# Regulator_3_3V.net
KiCad netlist of a schematic drawn in Altium Designer
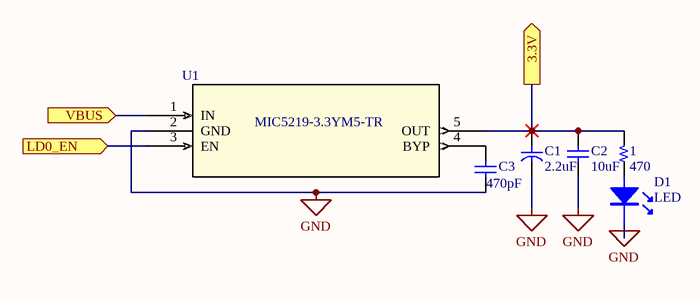
[diagram p0: Regulator 3.3V.SchDoc]

(export (version "E")
  (design (tool "Eeschema 10.0.6"))
  (components
    (comp (ref "1")
      (value "470")
      (footprint "R 0805")
      (description "Resistor")
      (libsource (lib "chipfc_libs") (part "Resistor"))
    )
    (comp (ref "C1")
      (value "2.2uF")
      (footprint "C SMD TAN 1206 (A)")
      (description "Capacitor pol")
      (libsource (lib "chipfc_libs") (part "Capacitor"))
    )
    (comp (ref "C2")
      (value "10uF")
      (footprint "C 0805")
      (description "Capacitor non-pol")
      (libsource (lib "chipfc_libs") (part "Capacitor NP"))
    )
    (comp (ref "C3")
      (value "470pF")
      (footprint "C 0805")
      (description "Capacitor non-pol")
      (libsource (lib "chipfc_libs") (part "Capacitor NP"))
    )
    (comp (ref "D1") (value "LED") (footprint "CAP10UF") (libsource (lib "Devzone_SCHLib") (part "LED")))
    (comp (ref "U1")
      (value "MIC5219-3.3YM5-TR")
      (footprint "SOT-23-5_M5_MCH")
      (description "No Description Available")
      (libsource (lib "MIC5219-3P3YM5-TR") (part "MIC5219-3.3YM5-TR"))
    )
  )
  (nets
    (net (code "1") (name "/3.3V") (class "Default")
      (node (ref "1") (pin "2") (pinfunction "2_2") (pintype "passive"))
      (node (ref "C1") (pin "1") (pinfunction "1_1") (pintype "passive"))
      (node (ref "C2") (pin "1") (pinfunction "1_1") (pintype "passive"))
      (node (ref "U1") (pin "5") (pinfunction "OUT_5") (pintype "output"))
    )
    (net (code "2") (name "/LD0_EN") (class "Default")
      (node (ref "U1") (pin "3") (pinfunction "EN_3") (pintype "input"))
    )
    (net (code "3") (name "/VBUS") (class "Default")
      (node (ref "U1") (pin "1") (pinfunction "IN_1") (pintype "input"))
    )
    (net (code "4") (name "GND") (class "Default")
      (node (ref "C1") (pin "2") (pinfunction "2_2") (pintype "passive"))
      (node (ref "C2") (pin "2") (pinfunction "2_2") (pintype "passive"))
      (node (ref "C3") (pin "2") (pinfunction "2_2") (pintype "passive"))
      (node (ref "D1") (pin "2") (pinfunction "2_2") (pintype "passive"))
      (node (ref "U1") (pin "2") (pinfunction "GND_2") (pintype "power_in"))
    )
    (net (code "5") (name "Net-(U1-BYP)") (class "Default")
      (node (ref "C3") (pin "1") (pinfunction "1_1") (pintype "passive"))
      (node (ref "U1") (pin "4") (pinfunction "BYP_4") (pintype "output"))
    )
    (net (code "6") (name "unconnected-(1-Pad1)") (class "Default")
      (node (ref "1") (pin "1") (pinfunction "1_1") (pintype "passive"))
    )
    (net (code "7") (name "unconnected-(D1-Pad1)") (class "Default")
      (node (ref "D1") (pin "1") (pinfunction "1_1") (pintype "passive"))
    )
  )
)
